# Main.net
KiCad netlist of a schematic drawn in Altium Designer
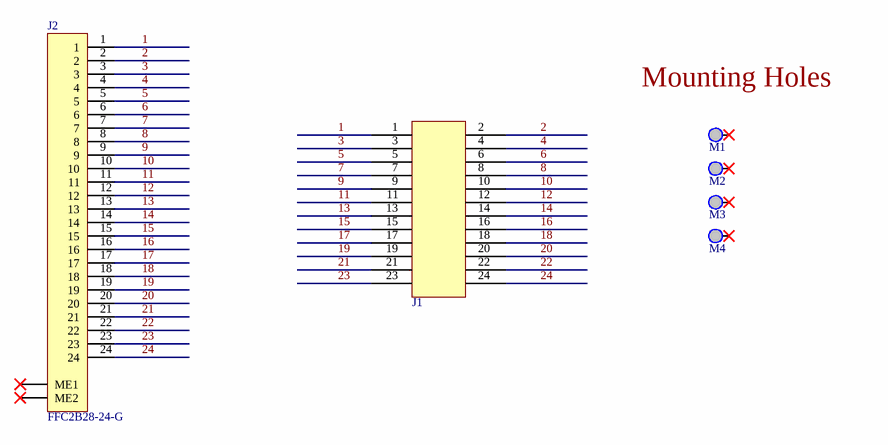
[diagram p0: Main.SchDoc]

(export (version "E")
  (design (tool "Eeschema 10.0.6"))
  (components
    (comp (ref "J1")
      (value "61302421121")
      (footprint "HDR-V-2X12-M-TH")
      (description "THT Vertical Pin Header WR-PHD, Pitch 2.54 mm, Dual Row, 24 pins")
      (libsource (lib "intercreate") (part "HDR-V-2X12-M"))
    )
    (comp (ref "J2")
      (value "FFC2B28-24-G")
      (footprint "CONN-FFC-H-24P-0.5MM")
      (description "24W, 0.5MM Ffc Con, R/a, Dual Cont,")
      (libsource (lib "intercreate") (part "CONN-FFC-H-24P-0.5MM"))
    )
    (comp (ref "M1")
      (value "MTG_HOLE")
      (footprint "MH_P_2.5MM")
      (description "MTG HOLE PLATED VARIOUS SIZES")
      (libsource (lib "intercreate") (part "MTG_HOLE"))
    )
    (comp (ref "M2")
      (value "MTG_HOLE")
      (footprint "MH_P_2.5MM")
      (description "MTG HOLE PLATED VARIOUS SIZES")
      (libsource (lib "intercreate") (part "MTG_HOLE"))
    )
    (comp (ref "M3")
      (value "MTG_HOLE")
      (footprint "MH_P_2.5MM")
      (description "MTG HOLE PLATED VARIOUS SIZES")
      (libsource (lib "intercreate") (part "MTG_HOLE"))
    )
    (comp (ref "M4")
      (value "MTG_HOLE")
      (footprint "MH_P_2.5MM")
      (description "MTG HOLE PLATED VARIOUS SIZES")
      (libsource (lib "intercreate") (part "MTG_HOLE"))
    )
  )
  (nets
    (net (code "1") (name "/1") (class "Default")
      (node (ref "J1") (pin "1") (pintype "passive"))
      (node (ref "J2") (pin "1") (pinfunction "1_1") (pintype "passive"))
    )
    (net (code "2") (name "/2") (class "Default")
      (node (ref "J1") (pin "2") (pintype "passive"))
      (node (ref "J2") (pin "2") (pinfunction "2_2") (pintype "passive"))
    )
    (net (code "3") (name "/3") (class "Default")
      (node (ref "J1") (pin "3") (pintype "passive"))
      (node (ref "J2") (pin "3") (pinfunction "3_3") (pintype "passive"))
    )
    (net (code "4") (name "/4") (class "Default")
      (node (ref "J1") (pin "4") (pintype "passive"))
      (node (ref "J2") (pin "4") (pinfunction "4_4") (pintype "passive"))
    )
    (net (code "5") (name "/5") (class "Default")
      (node (ref "J1") (pin "5") (pintype "passive"))
      (node (ref "J2") (pin "5") (pinfunction "5_5") (pintype "passive"))
    )
    (net (code "6") (name "/6") (class "Default")
      (node (ref "J1") (pin "6") (pintype "passive"))
      (node (ref "J2") (pin "6") (pinfunction "6_6") (pintype "passive"))
    )
    (net (code "7") (name "/7") (class "Default")
      (node (ref "J1") (pin "7") (pintype "passive"))
      (node (ref "J2") (pin "7") (pinfunction "7_7") (pintype "passive"))
    )
    (net (code "8") (name "/8") (class "Default")
      (node (ref "J1") (pin "8") (pintype "passive"))
      (node (ref "J2") (pin "8") (pinfunction "8_8") (pintype "passive"))
    )
    (net (code "9") (name "/9") (class "Default")
      (node (ref "J1") (pin "9") (pintype "passive"))
      (node (ref "J2") (pin "9") (pinfunction "9_9") (pintype "passive"))
    )
    (net (code "10") (name "/10") (class "Default")
      (node (ref "J1") (pin "10") (pintype "passive"))
      (node (ref "J2") (pin "10") (pinfunction "10_10") (pintype "passive"))
    )
    (net (code "11") (name "/11") (class "Default")
      (node (ref "J1") (pin "11") (pintype "passive"))
      (node (ref "J2") (pin "11") (pinfunction "11_11") (pintype "passive"))
    )
    (net (code "12") (name "/12") (class "Default")
      (node (ref "J1") (pin "12") (pintype "passive"))
      (node (ref "J2") (pin "12") (pinfunction "12_12") (pintype "passive"))
    )
    (net (code "13") (name "/13") (class "Default")
      (node (ref "J1") (pin "13") (pintype "passive"))
      (node (ref "J2") (pin "13") (pinfunction "13_13") (pintype "passive"))
    )
    (net (code "14") (name "/14") (class "Default")
      (node (ref "J1") (pin "14") (pintype "passive"))
      (node (ref "J2") (pin "14") (pinfunction "14_14") (pintype "passive"))
    )
    (net (code "15") (name "/15") (class "Default")
      (node (ref "J1") (pin "15") (pintype "passive"))
      (node (ref "J2") (pin "15") (pinfunction "15_15") (pintype "passive"))
    )
    (net (code "16") (name "/16") (class "Default")
      (node (ref "J1") (pin "16") (pintype "passive"))
      (node (ref "J2") (pin "16") (pinfunction "16_16") (pintype "passive"))
    )
    (net (code "17") (name "/17") (class "Default")
      (node (ref "J1") (pin "17") (pintype "passive"))
      (node (ref "J2") (pin "17") (pinfunction "17_17") (pintype "passive"))
    )
    (net (code "18") (name "/18") (class "Default")
      (node (ref "J1") (pin "18") (pintype "passive"))
      (node (ref "J2") (pin "18") (pinfunction "18_18") (pintype "passive"))
    )
    (net (code "19") (name "/19") (class "Default")
      (node (ref "J1") (pin "19") (pintype "passive"))
      (node (ref "J2") (pin "19") (pinfunction "19_19") (pintype "passive"))
    )
    (net (code "20") (name "/20") (class "Default")
      (node (ref "J1") (pin "20") (pintype "passive"))
      (node (ref "J2") (pin "20") (pinfunction "20_20") (pintype "passive"))
    )
    (net (code "21") (name "/21") (class "Default")
      (node (ref "J1") (pin "21") (pintype "passive"))
      (node (ref "J2") (pin "21") (pinfunction "21_21") (pintype "passive"))
    )
    (net (code "22") (name "/22") (class "Default")
      (node (ref "J1") (pin "22") (pintype "passive"))
      (node (ref "J2") (pin "22") (pinfunction "22_22") (pintype "passive"))
    )
    (net (code "23") (name "/23") (class "Default")
      (node (ref "J1") (pin "23") (pintype "passive"))
      (node (ref "J2") (pin "23") (pinfunction "23_23") (pintype "passive"))
    )
    (net (code "24") (name "/24") (class "Default")
      (node (ref "J1") (pin "24") (pintype "passive"))
      (node (ref "J2") (pin "24") (pinfunction "24_24") (pintype "passive"))
    )
    (net (code "25") (name "unconnected-(J2-PadME1)") (class "Default")
      (node (ref "J2") (pin "ME1") (pinfunction "ME1_ME1") (pintype "passive+no_connect"))
    )
    (net (code "26") (name "unconnected-(J2-PadME2)") (class "Default")
      (node (ref "J2") (pin "ME2") (pinfunction "ME2_ME2") (pintype "passive+no_connect"))
    )
    (net (code "27") (name "unconnected-(M1-Pad1)") (class "Default")
      (node (ref "M1") (pin "1") (pinfunction "1_1") (pintype "passive+no_connect"))
    )
    (net (code "28") (name "unconnected-(M2-Pad1)") (class "Default")
      (node (ref "M2") (pin "1") (pinfunction "1_1") (pintype "passive+no_connect"))
    )
    (net (code "29") (name "unconnected-(M3-Pad1)") (class "Default")
      (node (ref "M3") (pin "1") (pinfunction "1_1") (pintype "passive+no_connect"))
    )
    (net (code "30") (name "unconnected-(M4-Pad1)") (class "Default")
      (node (ref "M4") (pin "1") (pinfunction "1_1") (pintype "passive+no_connect"))
    )
  )
)
